# ET-DAC.net
KiCad netlist of a schematic drawn in Altium Designer
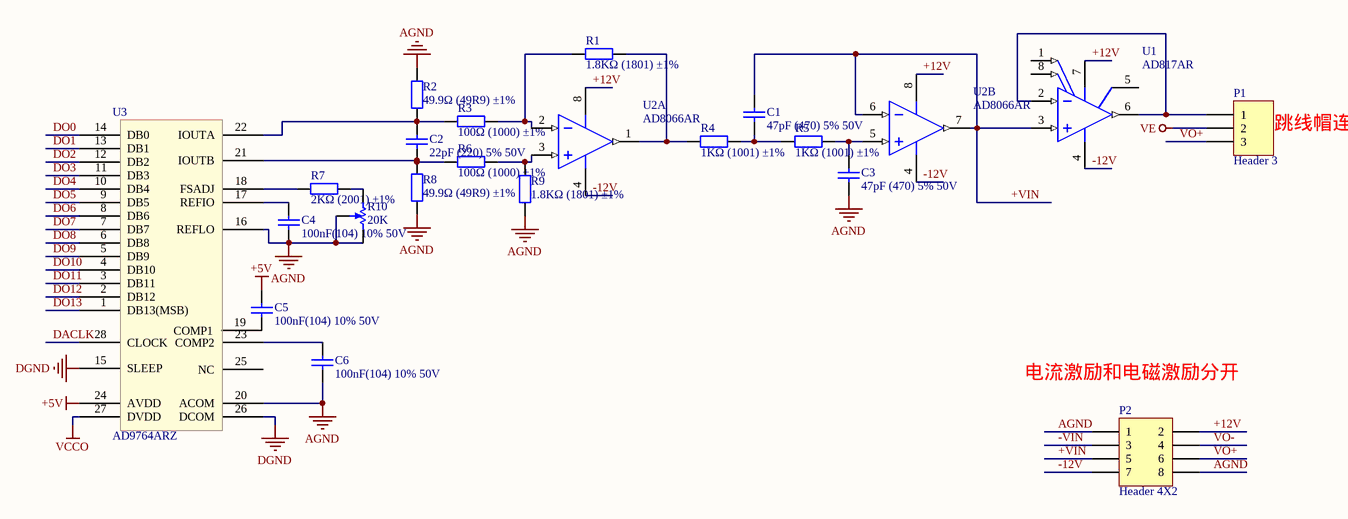
[diagram p0: ET-DAC.SchDoc]

(export (version "E")
  (design (tool "Eeschema 10.0.6"))
  (components
    (comp (ref "C1")
      (value "47pF (470) 5% 50V")
      (footprint "LC-0805_C")
      (description "贴片电容")
      (libsource (lib "Miscellaneous Devices LC") (part "0805 47pF (470) 5% 50V"))
    )
    (comp (ref "C2")
      (value "22pF (220) 5% 50V")
      (footprint "LC-0805_C")
      (description "贴片电容")
      (libsource (lib "Miscellaneous Devices LC") (part "0805 22pF (220) 5% 50V"))
    )
    (comp (ref "C3")
      (value "47pF (470) 5% 50V")
      (footprint "LC-0805_C")
      (description "贴片电容")
      (libsource (lib "Miscellaneous Devices LC") (part "0805 47pF (470) 5% 50V"))
    )
    (comp (ref "C4")
      (value "100nF(104) 10% 50V")
      (footprint "LC-0805_C")
      (description "贴片电容")
      (libsource (lib "Miscellaneous Devices LC") (part "0805 100nF(104) 10% 50V"))
    )
    (comp (ref "C5")
      (value "100nF(104) 10% 50V")
      (footprint "LC-0805_C")
      (description "贴片电容")
      (libsource (lib "Miscellaneous Devices LC") (part "0805 100nF(104) 10% 50V"))
    )
    (comp (ref "C6")
      (value "100nF(104) 10% 50V")
      (footprint "LC-0805_C")
      (description "贴片电容")
      (libsource (lib "Miscellaneous Devices LC") (part "0805 100nF(104) 10% 50V"))
    )
    (comp (ref "P1")
      (value "Header 3")
      (footprint "HDR1X3")
      (description "Header, 3-Pin")
      (fields (field (name "PUBLISHER") "Altium Limited"))
      (libsource (lib "Miscellaneous Connectors") (part "Header 3"))
    )
    (comp (ref "P2")
      (value "Header 4X2")
      (footprint "HDR2X4")
      (description "Header, 4-Pin, Dual row")
      (fields (field (name "PUBLISHER") "Altium Limited"))
      (libsource (lib "Miscellaneous Connectors") (part "Header 4X2"))
    )
    (comp (ref "R1")
      (value "1.8KΩ (1801) ±1%")
      (footprint "LC-0805_R")
      (description "贴片电阻")
      (libsource (lib "Miscellaneous Devices LC") (part "0805 1.8KΩ (1801) 1%"))
    )
    (comp (ref "R2")
      (value "49.9Ω (49R9) ±1%")
      (footprint "LC-0805_R")
      (description "贴片电阻")
      (libsource (lib "Miscellaneous Devices LC") (part "0805 49.9Ω (49R9) 1%"))
    )
    (comp (ref "R3")
      (value "100Ω (1000) ±1%")
      (footprint "LC-0805_R")
      (description "贴片电阻")
      (libsource (lib "Miscellaneous Devices LC") (part "0805 100Ω (1000) 1%"))
    )
    (comp (ref "R4")
      (value "1KΩ (1001) ±1%")
      (footprint "LC-0805_R")
      (description "贴片电阻")
      (libsource (lib "") (part "0805 1KΩ (1001) 1%_1"))
    )
    (comp (ref "R5")
      (value "1KΩ (1001) ±1%")
      (footprint "LC-0805_R")
      (description "贴片电阻")
      (libsource (lib "Miscellaneous Devices LC") (part "0805 1KΩ (1001) 1%"))
    )
    (comp (ref "R6")
      (value "100Ω (1000) ±1%")
      (footprint "LC-0805_R")
      (description "贴片电阻")
      (libsource (lib "Miscellaneous Devices LC") (part "0805 100Ω (1000) 1%"))
    )
    (comp (ref "R7")
      (value "2KΩ (2001) ±1%")
      (footprint "LC-0805_R")
      (description "贴片电阻")
      (libsource (lib "Miscellaneous Devices LC") (part "0805 2KΩ (2001) 1%"))
    )
    (comp (ref "R8")
      (value "49.9Ω (49R9) ±1%")
      (footprint "LC-0805_R")
      (description "贴片电阻")
      (libsource (lib "Miscellaneous Devices LC") (part "0805 49.9Ω (49R9) 1%"))
    )
    (comp (ref "R9")
      (value "1.8KΩ (1801) ±1%")
      (footprint "LC-0805_R")
      (description "贴片电阻")
      (libsource (lib "") (part "0805 1.8KΩ (1801) 1%_1"))
    )
    (comp (ref "R10")
      (value "20K")
      (footprint "POT4MM-2")
      (description "Square Trimming Potentiometer")
      (fields (field (name "PUBLISHER") "Altium Limited"))
      (libsource (lib "Miscellaneous Devices") (part "RPot SM"))
    )
    (comp (ref "U1")
      (value "AD817AR")
      (footprint "ADI-R-8_N")
      (fields (field (name "GENERIC PART NUMBER") "AD817") (field (name "MANUFACTURER") "Analog Devices"))
      (libsource (lib "Analog Devices Operational Amplifiers") (part "AD817AR"))
    )
    (comp (ref "U2")
      (value "AD8066AR")
      (footprint "ADI-R-8_N")
      (fields (field (name "GENERIC PART NUMBER") "AD8066") (field (name "MANUFACTURER") "Analog Devices"))
      (libsource (lib "Analog Devices Operational Amplifiers") (part "AD8066AR"))
    )
    (comp (ref "U3")
      (value "AD9764ARZ")
      (footprint "RW_28")
      (description "Imported")
      (libsource (lib "AD9764ARZ") (part "AD9764ARZ"))
    )
  )
  (nets
    (net (code "1") (name "+5V") (class "Default")
      (node (ref "C5") (pin "2") (pinfunction "2_2") (pintype "passive"))
      (node (ref "U3") (pin "24") (pinfunction "AVDD_24") (pintype "power_in"))
    )
    (net (code "2") (name "/+12V") (class "Default")
      (node (ref "P2") (pin "2") (pinfunction "2_2") (pintype "passive"))
      (node (ref "U1") (pin "7") (pinfunction "+VS_7") (pintype "power_in"))
      (node (ref "U2") (pin "8") (pinfunction "+VS_8") (pintype "power_in"))
    )
    (net (code "3") (name "/+VIN") (class "Default")
      (node (ref "C1") (pin "2") (pinfunction "2_2") (pintype "passive"))
      (node (ref "P2") (pin "5") (pinfunction "5_5") (pintype "passive"))
      (node (ref "U1") (pin "3") (pinfunction "+IN_3") (pintype "input"))
      (node (ref "U2") (pin "6") (pinfunction "-IN_2_6") (pintype "input"))
      (node (ref "U2") (pin "7") (pinfunction "VOUT_2_7") (pintype "output"))
    )
    (net (code "4") (name "/-12V") (class "Default")
      (node (ref "P2") (pin "7") (pinfunction "7_7") (pintype "passive"))
      (node (ref "U1") (pin "4") (pinfunction "-VS_4") (pintype "power_in"))
      (node (ref "U2") (pin "4") (pinfunction "-VS_4") (pintype "power_in"))
    )
    (net (code "5") (name "/-VIN") (class "Default")
      (node (ref "P2") (pin "3") (pinfunction "3_3") (pintype "passive"))
    )
    (net (code "6") (name "/DACLK") (class "Default")
      (node (ref "U3") (pin "28") (pinfunction "CLOCK_28") (pintype "passive"))
    )
    (net (code "7") (name "/DO0") (class "Default")
      (node (ref "U3") (pin "14") (pinfunction "DB0_14") (pintype "passive"))
    )
    (net (code "8") (name "/DO1") (class "Default")
      (node (ref "U3") (pin "13") (pinfunction "DB1_13") (pintype "passive"))
    )
    (net (code "9") (name "/DO2") (class "Default")
      (node (ref "U3") (pin "12") (pinfunction "DB2_12") (pintype "passive"))
    )
    (net (code "10") (name "/DO3") (class "Default")
      (node (ref "U3") (pin "11") (pinfunction "DB3_11") (pintype "passive"))
    )
    (net (code "11") (name "/DO4") (class "Default")
      (node (ref "U3") (pin "10") (pinfunction "DB4_10") (pintype "passive"))
    )
    (net (code "12") (name "/DO5") (class "Default")
      (node (ref "U3") (pin "9") (pinfunction "DB5_9") (pintype "passive"))
    )
    (net (code "13") (name "/DO6") (class "Default")
      (node (ref "U3") (pin "8") (pinfunction "DB6_8") (pintype "passive"))
    )
    (net (code "14") (name "/DO7") (class "Default")
      (node (ref "U3") (pin "7") (pinfunction "DB7_7") (pintype "passive"))
    )
    (net (code "15") (name "/DO8") (class "Default")
      (node (ref "U3") (pin "6") (pinfunction "DB8_6") (pintype "passive"))
    )
    (net (code "16") (name "/DO9") (class "Default")
      (node (ref "U3") (pin "5") (pinfunction "DB9_5") (pintype "passive"))
    )
    (net (code "17") (name "/DO10") (class "Default")
      (node (ref "U3") (pin "4") (pinfunction "DB10_4") (pintype "passive"))
    )
    (net (code "18") (name "/DO11") (class "Default")
      (node (ref "U3") (pin "3") (pinfunction "DB11_3") (pintype "passive"))
    )
    (net (code "19") (name "/DO12") (class "Default")
      (node (ref "U3") (pin "2") (pinfunction "DB12_2") (pintype "passive"))
    )
    (net (code "20") (name "/DO13") (class "Default")
      (node (ref "U3") (pin "1") (pinfunction "DB13(MSB)_1") (pintype "passive"))
    )
    (net (code "21") (name "/VO+") (class "Default")
      (node (ref "P1") (pin "3") (pinfunction "3_3") (pintype "passive"))
      (node (ref "P2") (pin "6") (pinfunction "6_6") (pintype "passive"))
    )
    (net (code "22") (name "/VO-") (class "Default")
      (node (ref "P2") (pin "4") (pinfunction "4_4") (pintype "passive"))
    )
    (net (code "23") (name "AGND") (class "Default")
      (node (ref "C3") (pin "2") (pinfunction "2_2") (pintype "passive"))
      (node (ref "C4") (pin "1") (pinfunction "1_1") (pintype "passive"))
      (node (ref "C6") (pin "1") (pinfunction "1_1") (pintype "passive"))
      (node (ref "P2") (pin "1") (pinfunction "1_1") (pintype "passive"))
      (node (ref "P2") (pin "8") (pinfunction "8_8") (pintype "passive"))
      (node (ref "R10") (pin "CW") (pinfunction "+_CW") (pintype "passive"))
      (node (ref "R10") (pin "W") (pinfunction "W_W") (pintype "passive"))
      (node (ref "R2") (pin "2") (pinfunction "2_2") (pintype "passive"))
      (node (ref "R8") (pin "1") (pinfunction "1_1") (pintype "passive"))
      (node (ref "R9") (pin "1") (pinfunction "1_1") (pintype "passive"))
      (node (ref "U3") (pin "16") (pinfunction "REFLO_16") (pintype "passive"))
      (node (ref "U3") (pin "20") (pinfunction "ACOM_20") (pintype "passive"))
    )
    (net (code "24") (name "DGND") (class "Default")
      (node (ref "U3") (pin "15") (pinfunction "SLEEP_15") (pintype "passive"))
      (node (ref "U3") (pin "26") (pinfunction "DCOM_26") (pintype "passive"))
    )
    (net (code "25") (name "Net-(C1-Pad1)") (class "Default")
      (node (ref "C1") (pin "1") (pinfunction "1_1") (pintype "passive"))
      (node (ref "R4") (pin "2") (pinfunction "2_2") (pintype "passive"))
      (node (ref "R5") (pin "2") (pinfunction "2_2") (pintype "passive"))
    )
    (net (code "26") (name "Net-(R10--)") (class "Default")
      (node (ref "R10") (pin "CCW") (pinfunction "-_CCW") (pintype "passive"))
      (node (ref "R7") (pin "2") (pinfunction "2_2") (pintype "passive"))
    )
    (net (code "27") (name "Net-(U1--IN)") (class "Default")
      (node (ref "P1") (pin "1") (pinfunction "1_1") (pintype "passive"))
      (node (ref "U1") (pin "2") (pinfunction "-IN_2") (pintype "input"))
      (node (ref "U1") (pin "6") (pinfunction "OUT_6") (pintype "output"))
    )
    (net (code "28") (name "Net-(U2A-+IN_1)") (class "Default")
      (node (ref "R6") (pin "2") (pinfunction "2_2") (pintype "passive"))
      (node (ref "R9") (pin "2") (pinfunction "2_2") (pintype "passive"))
      (node (ref "U2") (pin "3") (pinfunction "+IN_1_3") (pintype "input"))
    )
    (net (code "29") (name "Net-(U2A--IN_1)") (class "Default")
      (node (ref "R1") (pin "1") (pinfunction "1_1") (pintype "passive"))
      (node (ref "R3") (pin "2") (pinfunction "2_2") (pintype "passive"))
      (node (ref "U2") (pin "2") (pinfunction "-IN_1_2") (pintype "input"))
    )
    (net (code "30") (name "Net-(U2A-VOUT_1)") (class "Default")
      (node (ref "R1") (pin "2") (pinfunction "2_2") (pintype "passive"))
      (node (ref "R4") (pin "1") (pinfunction "1_1") (pintype "passive"))
      (node (ref "U2") (pin "1") (pinfunction "VOUT_1_1") (pintype "output"))
    )
    (net (code "31") (name "Net-(U2B-+IN_2)") (class "Default")
      (node (ref "C3") (pin "1") (pinfunction "1_1") (pintype "passive"))
      (node (ref "R5") (pin "1") (pinfunction "1_1") (pintype "passive"))
      (node (ref "U2") (pin "5") (pinfunction "+IN_2_5") (pintype "input"))
    )
    (net (code "32") (name "Net-(U3-COMP1)") (class "Default")
      (node (ref "C5") (pin "1") (pinfunction "1_1") (pintype "passive"))
      (node (ref "U3") (pin "19") (pinfunction "COMP1_19") (pintype "passive"))
    )
    (net (code "33") (name "Net-(U3-COMP2)") (class "Default")
      (node (ref "C6") (pin "2") (pinfunction "2_2") (pintype "passive"))
      (node (ref "U3") (pin "23") (pinfunction "COMP2_23") (pintype "passive"))
    )
    (net (code "34") (name "Net-(U3-FSADJ)") (class "Default")
      (node (ref "R7") (pin "1") (pinfunction "1_1") (pintype "passive"))
      (node (ref "U3") (pin "18") (pinfunction "FSADJ_18") (pintype "passive"))
    )
    (net (code "35") (name "Net-(U3-IOUTA)") (class "Default")
      (node (ref "C2") (pin "2") (pinfunction "2_2") (pintype "passive"))
      (node (ref "R2") (pin "1") (pinfunction "1_1") (pintype "passive"))
      (node (ref "R3") (pin "1") (pinfunction "1_1") (pintype "passive"))
      (node (ref "U3") (pin "22") (pinfunction "IOUTA_22") (pintype "passive"))
    )
    (net (code "36") (name "Net-(U3-IOUTB)") (class "Default")
      (node (ref "C2") (pin "1") (pinfunction "1_1") (pintype "passive"))
      (node (ref "R6") (pin "1") (pinfunction "1_1") (pintype "passive"))
      (node (ref "R8") (pin "2") (pinfunction "2_2") (pintype "passive"))
      (node (ref "U3") (pin "21") (pinfunction "IOUTB_21") (pintype "passive"))
    )
    (net (code "37") (name "Net-(U3-REFIO)") (class "Default")
      (node (ref "C4") (pin "2") (pinfunction "2_2") (pintype "passive"))
      (node (ref "U3") (pin "17") (pinfunction "REFIO_17") (pintype "passive"))
    )
    (net (code "38") (name "VCCO") (class "Default")
      (node (ref "U3") (pin "27") (pinfunction "DVDD_27") (pintype "power_in"))
    )
    (net (code "39") (name "VE") (class "Default")
      (node (ref "P1") (pin "2") (pinfunction "2_2") (pintype "passive"))
    )
    (net (code "40") (name "unconnected-(U1-NC-Pad5)") (class "Default")
      (node (ref "U1") (pin "5") (pinfunction "NC_5") (pintype "passive"))
    )
    (net (code "41") (name "unconnected-(U1-NULL-Pad1)") (class "Default")
      (node (ref "U1") (pin "1") (pinfunction "NULL_1") (pintype "input"))
    )
    (net (code "42") (name "unconnected-(U1-NULL-Pad8)") (class "Default")
      (node (ref "U1") (pin "8") (pinfunction "NULL_8") (pintype "input"))
    )
    (net (code "43") (name "unconnected-(U3-NC-Pad25)") (class "Default")
      (node (ref "U3") (pin "25") (pinfunction "NC_25") (pintype "passive"))
    )
  )
)
